# EEG.net
KiCad netlist of a schematic drawn in EAGLE
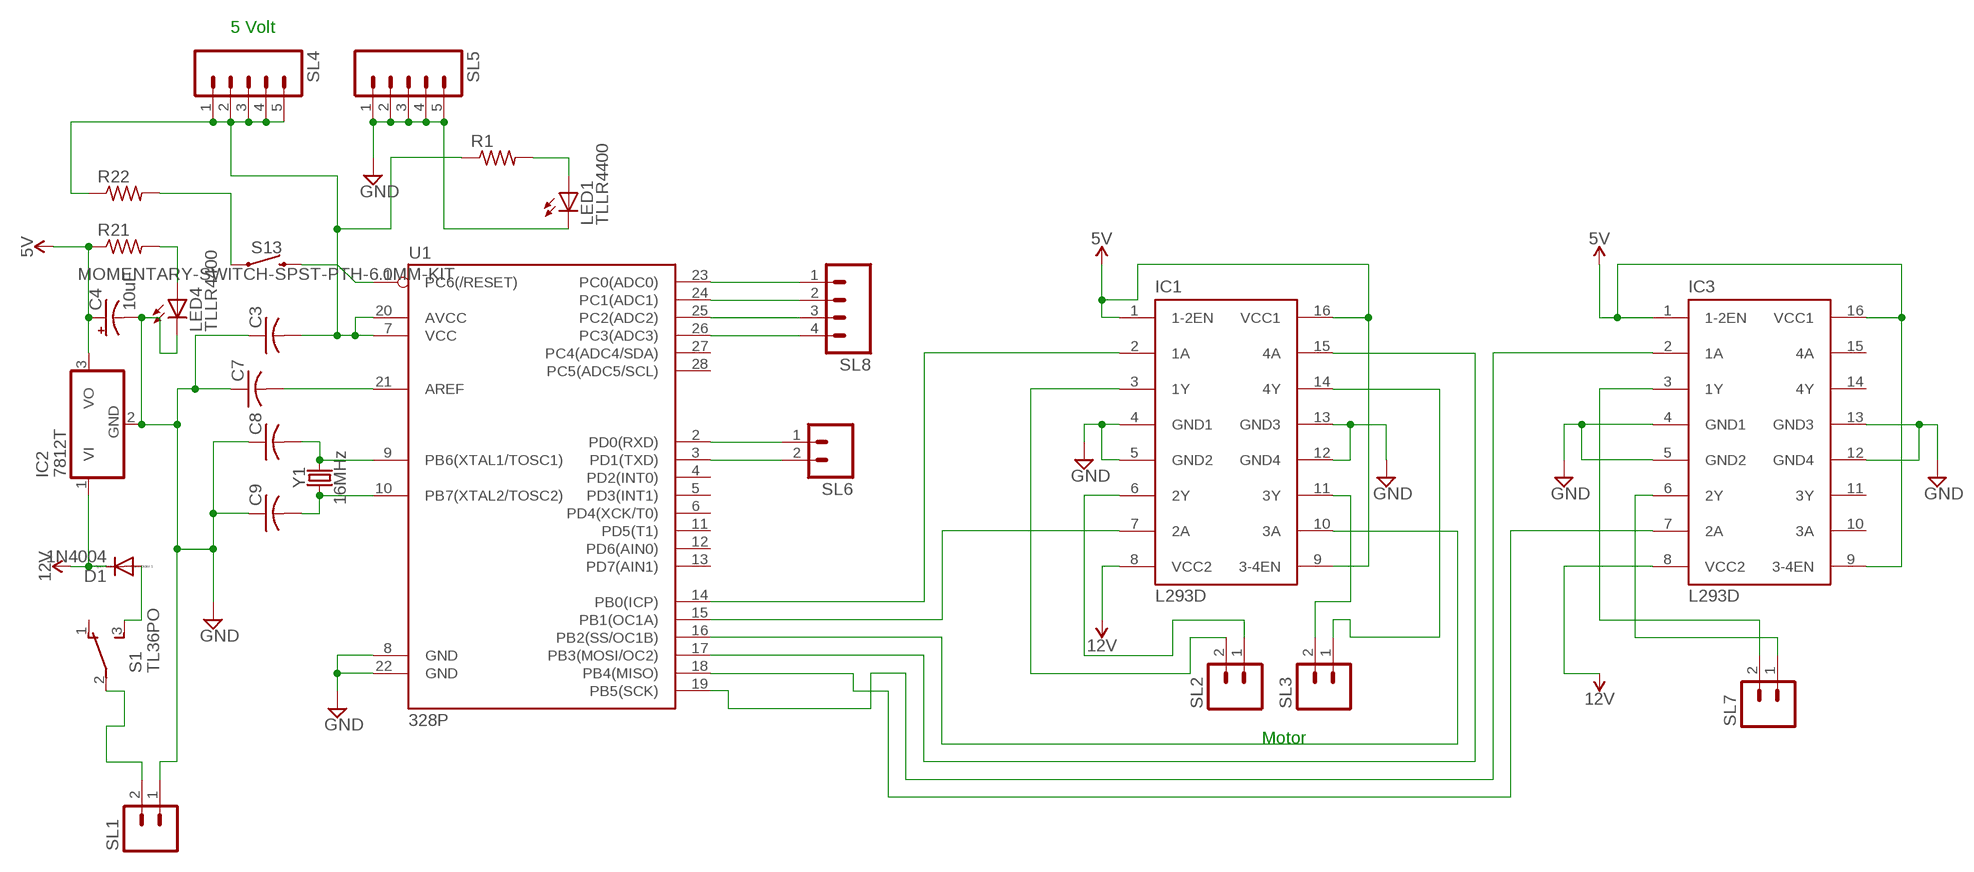
[diagram p0: schematic, sheet 1]

(export (version "E")
  (design (tool "Eeschema 10.0.6"))
  (components
    (comp (ref "C3")
      (value "C-US025-025X050")
      (footprint "eagle-import:C025-025X050")
      (libsource (lib "eagle-import") (part "C-US025-025X050"))
    )
    (comp (ref "C4")
      (value "10uF")
      (footprint "eagle-import:CPOL-RADIAL-2.5MM-5MM-KIT")
      (libsource (lib "eagle-import") (part "10UF-POLAR-RADIAL-2.5MM-KIT-25V-20%"))
    )
    (comp (ref "C7")
      (value "C-US025-025X050")
      (footprint "eagle-import:C025-025X050")
      (libsource (lib "eagle-import") (part "C-US025-025X050"))
    )
    (comp (ref "C8")
      (value "C-US025-025X050")
      (footprint "eagle-import:C025-025X050")
      (libsource (lib "eagle-import") (part "C-US025-025X050"))
    )
    (comp (ref "C9")
      (value "C-US025-025X050")
      (footprint "eagle-import:C025-025X050")
      (libsource (lib "eagle-import") (part "C-US025-025X050"))
    )
    (comp (ref "D1")
      (value "1N4004")
      (footprint "eagle-import:DO41-10")
      (libsource (lib "eagle-import") (part "1N4004"))
    )
    (comp (ref "IC1")
      (value "L293D")
      (footprint "eagle-import:DIL16")
      (libsource (lib "eagle-import") (part "L293D"))
    )
    (comp (ref "IC2")
      (value "7812T")
      (footprint "eagle-import:TO220H")
      (libsource (lib "eagle-import") (part "78T12"))
    )
    (comp (ref "IC3")
      (value "L293D")
      (footprint "eagle-import:DIL16")
      (libsource (lib "eagle-import") (part "L293D"))
    )
    (comp (ref "LED1")
      (value "TLLR4400")
      (footprint "eagle-import:LED3MM")
      (fields (field (name "MF") "VISHAY SEMICONDUCTOR"))
      (libsource (lib "eagle-import") (part "TLLR4400"))
    )
    (comp (ref "LED4")
      (value "TLLR4400")
      (footprint "eagle-import:LED3MM")
      (fields (field (name "MF") "VISHAY SEMICONDUCTOR"))
      (libsource (lib "eagle-import") (part "TLLR4400"))
    )
    (comp (ref "R1")
      (value "R-US_0207/12")
      (footprint "eagle-import:0207_12")
      (libsource (lib "eagle-import") (part "R-US_0207/12"))
    )
    (comp (ref "R21")
      (value "R-US_0207/12")
      (footprint "eagle-import:0207_12")
      (libsource (lib "eagle-import") (part "R-US_0207/12"))
    )
    (comp (ref "R22")
      (value "R-US_0207/12")
      (footprint "eagle-import:0207_12")
      (libsource (lib "eagle-import") (part "R-US_0207/12"))
    )
    (comp (ref "S1")
      (value "TL36PO")
      (footprint "eagle-import:TL3XPO")
      (libsource (lib "eagle-import") (part "TL36PO"))
    )
    (comp (ref "S13")
      (value "MOMENTARY-SWITCH-SPST-PTH-6.0MM-KIT")
      (footprint "eagle-import:TACTILE_SWITCH_PTH_6.0MM_KIT")
      (libsource (lib "eagle-import") (part "MOMENTARY-SWITCH-SPST-PTH-6.0MM-KIT"))
    )
    (comp (ref "SL1")
      (value "MA02")
      (footprint "eagle-import:02PA")
      (libsource (lib "eagle-import") (part "MA02"))
    )
    (comp (ref "SL2")
      (value "MA02")
      (footprint "eagle-import:02PA")
      (libsource (lib "eagle-import") (part "MA02"))
    )
    (comp (ref "SL3")
      (value "MA02")
      (footprint "eagle-import:02PA")
      (libsource (lib "eagle-import") (part "MA02"))
    )
    (comp (ref "SL4")
      (value "MA05")
      (footprint "eagle-import:05PA")
      (libsource (lib "eagle-import") (part "MA05"))
    )
    (comp (ref "SL5")
      (value "MA05")
      (footprint "eagle-import:05PA")
      (libsource (lib "eagle-import") (part "MA05"))
    )
    (comp (ref "SL6")
      (value "MA02")
      (footprint "eagle-import:02PA")
      (libsource (lib "eagle-import") (part "MA02"))
    )
    (comp (ref "SL7")
      (value "MA02")
      (footprint "eagle-import:02PA")
      (libsource (lib "eagle-import") (part "MA02"))
    )
    (comp (ref "SL8")
      (value "MA04")
      (footprint "eagle-import:04PA")
      (libsource (lib "eagle-import") (part "MA04"))
    )
    (comp (ref "U1")
      (value "328P")
      (footprint "eagle-import:DIP28")
      (libsource (lib "eagle-import") (part "ATMEGA328P_PDIP"))
    )
    (comp (ref "Y1")
      (value "16MHz")
      (footprint "eagle-import:HC49US")
      (libsource (lib "eagle-import") (part "CRYSTAL-16MHZPTH-HC49US"))
    )
  )
  (nets
    (net (code "1") (name "5V") (class "Default")
      (node (ref "C4") (pin "1") (pinfunction "+_1") (pintype "passive"))
      (node (ref "IC1") (pin "1") (pinfunction "1-2EN_1") (pintype "input"))
      (node (ref "IC1") (pin "16") (pinfunction "VCC1_16") (pintype "power_in"))
      (node (ref "IC1") (pin "9") (pinfunction "3-4EN_9") (pintype "input"))
      (node (ref "IC2") (pin "3") (pinfunction "VO_3") (pintype "passive"))
      (node (ref "IC3") (pin "1") (pinfunction "1-2EN_1") (pintype "input"))
      (node (ref "IC3") (pin "16") (pinfunction "VCC1_16") (pintype "power_in"))
      (node (ref "IC3") (pin "9") (pinfunction "3-4EN_9") (pintype "input"))
      (node (ref "R21") (pin "1") (pinfunction "1_1") (pintype "passive"))
    )
    (net (code "2") (name "12V") (class "Default")
      (node (ref "D1") (pin "C") (pinfunction "C_C") (pintype "passive"))
      (node (ref "IC1") (pin "8") (pinfunction "VCC2_8") (pintype "power_in"))
      (node (ref "IC2") (pin "1") (pinfunction "VI_1") (pintype "input"))
      (node (ref "IC3") (pin "8") (pinfunction "VCC2_8") (pintype "power_in"))
    )
    (net (code "3") (name "GND") (class "Default")
      (node (ref "C3") (pin "1") (pinfunction "1_1") (pintype "passive"))
      (node (ref "C4") (pin "2") (pinfunction "-_2") (pintype "passive"))
      (node (ref "C7") (pin "1") (pinfunction "1_1") (pintype "passive"))
      (node (ref "C8") (pin "1") (pinfunction "1_1") (pintype "passive"))
      (node (ref "C9") (pin "1") (pinfunction "1_1") (pintype "passive"))
      (node (ref "IC1") (pin "12") (pinfunction "GND4_12") (pintype "power_in"))
      (node (ref "IC1") (pin "13") (pinfunction "GND3_13") (pintype "power_in"))
      (node (ref "IC1") (pin "4") (pinfunction "GND1_4") (pintype "power_in"))
      (node (ref "IC1") (pin "5") (pinfunction "GND2_5") (pintype "power_in"))
      (node (ref "IC2") (pin "2") (pinfunction "GND_2") (pintype "passive"))
      (node (ref "IC3") (pin "12") (pinfunction "GND4_12") (pintype "power_in"))
      (node (ref "IC3") (pin "13") (pinfunction "GND3_13") (pintype "power_in"))
      (node (ref "IC3") (pin "4") (pinfunction "GND1_4") (pintype "power_in"))
      (node (ref "IC3") (pin "5") (pinfunction "GND2_5") (pintype "power_in"))
      (node (ref "LED1") (pin "K") (pinfunction "C_K") (pintype "passive"))
      (node (ref "LED4") (pin "K") (pinfunction "C_K") (pintype "passive"))
      (node (ref "SL1") (pin "1") (pinfunction "1_1") (pintype "passive"))
      (node (ref "SL5") (pin "1") (pinfunction "1_1") (pintype "passive"))
      (node (ref "SL5") (pin "2") (pinfunction "2_2") (pintype "passive"))
      (node (ref "SL5") (pin "3") (pinfunction "3_3") (pintype "passive"))
      (node (ref "SL5") (pin "4") (pinfunction "4_4") (pintype "passive"))
      (node (ref "SL5") (pin "5") (pinfunction "5_5") (pintype "passive"))
      (node (ref "U1") (pin "22") (pinfunction "GND_22") (pintype "bidirectional"))
      (node (ref "U1") (pin "8") (pinfunction "GND_8") (pintype "bidirectional"))
    )
    (net (code "4") (name "Net-(IC1-1A)") (class "Default")
      (node (ref "IC1") (pin "2") (pinfunction "1A_2") (pintype "input"))
      (node (ref "U1") (pin "14") (pinfunction "PB0(ICP)_14") (pintype "bidirectional"))
    )
    (net (code "5") (name "Net-(IC1-1Y)") (class "Default")
      (node (ref "IC1") (pin "3") (pinfunction "1Y_3") (pintype "output"))
      (node (ref "SL2") (pin "2") (pinfunction "2_2") (pintype "passive"))
    )
    (net (code "6") (name "Net-(IC1-2A)") (class "Default")
      (node (ref "IC1") (pin "7") (pinfunction "2A_7") (pintype "input"))
      (node (ref "U1") (pin "15") (pinfunction "PB1(OC1A)_15") (pintype "bidirectional"))
    )
    (net (code "7") (name "Net-(IC1-2Y)") (class "Default")
      (node (ref "IC1") (pin "6") (pinfunction "2Y_6") (pintype "output"))
      (node (ref "SL2") (pin "1") (pinfunction "1_1") (pintype "passive"))
    )
    (net (code "8") (name "Net-(IC1-3A)") (class "Default")
      (node (ref "IC1") (pin "10") (pinfunction "3A_10") (pintype "input"))
      (node (ref "U1") (pin "16") (pinfunction "PB2(SS/OC1B)_16") (pintype "bidirectional"))
    )
    (net (code "9") (name "Net-(IC1-3Y)") (class "Default")
      (node (ref "IC1") (pin "11") (pinfunction "3Y_11") (pintype "output"))
      (node (ref "SL3") (pin "2") (pinfunction "2_2") (pintype "passive"))
    )
    (net (code "10") (name "Net-(IC1-4A)") (class "Default")
      (node (ref "IC1") (pin "15") (pinfunction "4A_15") (pintype "input"))
      (node (ref "U1") (pin "17") (pinfunction "PB3(MOSI/OC2)_17") (pintype "bidirectional"))
    )
    (net (code "11") (name "Net-(IC1-4Y)") (class "Default")
      (node (ref "IC1") (pin "14") (pinfunction "4Y_14") (pintype "output"))
      (node (ref "SL3") (pin "1") (pinfunction "1_1") (pintype "passive"))
    )
    (net (code "12") (name "Net-(IC3-1A)") (class "Default")
      (node (ref "IC3") (pin "2") (pinfunction "1A_2") (pintype "input"))
      (node (ref "U1") (pin "19") (pinfunction "PB5(SCK)_19") (pintype "bidirectional"))
    )
    (net (code "13") (name "Net-(IC3-1Y)") (class "Default")
      (node (ref "IC3") (pin "3") (pinfunction "1Y_3") (pintype "output"))
      (node (ref "SL7") (pin "2") (pinfunction "2_2") (pintype "passive"))
    )
    (net (code "14") (name "Net-(IC3-2A)") (class "Default")
      (node (ref "IC3") (pin "7") (pinfunction "2A_7") (pintype "input"))
      (node (ref "U1") (pin "18") (pinfunction "PB4(MISO)_18") (pintype "bidirectional"))
    )
    (net (code "15") (name "Net-(IC3-2Y)") (class "Default")
      (node (ref "IC3") (pin "6") (pinfunction "2Y_6") (pintype "output"))
      (node (ref "SL7") (pin "1") (pinfunction "1_1") (pintype "passive"))
    )
    (net (code "16") (name "Net-(LED1-PadA)") (class "Default")
      (node (ref "LED1") (pin "A") (pinfunction "A_A") (pintype "passive"))
      (node (ref "R1") (pin "2") (pinfunction "2_2") (pintype "passive"))
    )
    (net (code "17") (name "Net-(LED4-PadA)") (class "Default")
      (node (ref "LED4") (pin "A") (pinfunction "A_A") (pintype "passive"))
      (node (ref "R21") (pin "2") (pinfunction "2_2") (pintype "passive"))
    )
    (net (code "18") (name "Net-(R22-Pad2)") (class "Default")
      (node (ref "R22") (pin "2") (pinfunction "2_2") (pintype "passive"))
      (node (ref "S13") (pin "1") (pinfunction "1_1") (pintype "passive"))
    )
    (net (code "19") (name "Net-(S1-P)") (class "Default")
      (node (ref "S1") (pin "2") (pinfunction "P_2") (pintype "passive"))
      (node (ref "SL1") (pin "2") (pinfunction "2_2") (pintype "passive"))
    )
    (net (code "20") (name "Net-(S1-S)") (class "Default")
      (node (ref "D1") (pin "A") (pinfunction "A_A") (pintype "passive"))
      (node (ref "S1") (pin "3") (pinfunction "S_3") (pintype "passive"))
    )
    (net (code "21") (name "Net-(S13-2)") (class "Default")
      (node (ref "S13") (pin "3") (pinfunction "2_3") (pintype "passive"))
      (node (ref "U1") (pin "1") (pinfunction "PC6(/RESET)_1") (pintype "bidirectional"))
    )
    (net (code "22") (name "Net-(U1-AREF)") (class "Default")
      (node (ref "C7") (pin "2") (pinfunction "2_2") (pintype "passive"))
      (node (ref "U1") (pin "21") (pinfunction "AREF_21") (pintype "bidirectional"))
    )
    (net (code "23") (name "Net-(U1-AVCC)") (class "Default")
      (node (ref "C3") (pin "2") (pinfunction "2_2") (pintype "passive"))
      (node (ref "R1") (pin "1") (pinfunction "1_1") (pintype "passive"))
      (node (ref "R22") (pin "1") (pinfunction "1_1") (pintype "passive"))
      (node (ref "SL4") (pin "1") (pinfunction "1_1") (pintype "passive"))
      (node (ref "SL4") (pin "2") (pinfunction "2_2") (pintype "passive"))
      (node (ref "SL4") (pin "3") (pinfunction "3_3") (pintype "passive"))
      (node (ref "SL4") (pin "4") (pinfunction "4_4") (pintype "passive"))
      (node (ref "SL4") (pin "5") (pinfunction "5_5") (pintype "passive"))
      (node (ref "U1") (pin "20") (pinfunction "AVCC_20") (pintype "bidirectional"))
      (node (ref "U1") (pin "7") (pinfunction "VCC_7") (pintype "bidirectional"))
    )
    (net (code "24") (name "Net-(U1-PB6(XTAL1{slash}TOSC1))") (class "Default")
      (node (ref "C8") (pin "2") (pinfunction "2_2") (pintype "passive"))
      (node (ref "U1") (pin "9") (pinfunction "PB6(XTAL1/TOSC1)_9") (pintype "bidirectional"))
      (node (ref "Y1") (pin "2") (pinfunction "2_2") (pintype "passive"))
    )
    (net (code "25") (name "Net-(U1-PB7(XTAL2{slash}TOSC2))") (class "Default")
      (node (ref "C9") (pin "2") (pinfunction "2_2") (pintype "passive"))
      (node (ref "U1") (pin "10") (pinfunction "PB7(XTAL2/TOSC2)_10") (pintype "bidirectional"))
      (node (ref "Y1") (pin "1") (pinfunction "1_1") (pintype "passive"))
    )
    (net (code "26") (name "Net-(U1-PC0(ADC0))") (class "Default")
      (node (ref "SL8") (pin "1") (pinfunction "1_1") (pintype "passive"))
      (node (ref "U1") (pin "23") (pinfunction "PC0(ADC0)_23") (pintype "bidirectional"))
    )
    (net (code "27") (name "Net-(U1-PC1(ADC1))") (class "Default")
      (node (ref "SL8") (pin "2") (pinfunction "2_2") (pintype "passive"))
      (node (ref "U1") (pin "24") (pinfunction "PC1(ADC1)_24") (pintype "bidirectional"))
    )
    (net (code "28") (name "Net-(U1-PC2(ADC2))") (class "Default")
      (node (ref "SL8") (pin "3") (pinfunction "3_3") (pintype "passive"))
      (node (ref "U1") (pin "25") (pinfunction "PC2(ADC2)_25") (pintype "bidirectional"))
    )
    (net (code "29") (name "Net-(U1-PC3(ADC3))") (class "Default")
      (node (ref "SL8") (pin "4") (pinfunction "4_4") (pintype "passive"))
      (node (ref "U1") (pin "26") (pinfunction "PC3(ADC3)_26") (pintype "bidirectional"))
    )
    (net (code "30") (name "Net-(U1-PD0(RXD))") (class "Default")
      (node (ref "SL6") (pin "1") (pinfunction "1_1") (pintype "passive"))
      (node (ref "U1") (pin "2") (pinfunction "PD0(RXD)_2") (pintype "bidirectional"))
    )
    (net (code "31") (name "Net-(U1-PD1(TXD))") (class "Default")
      (node (ref "SL6") (pin "2") (pinfunction "2_2") (pintype "passive"))
      (node (ref "U1") (pin "3") (pinfunction "PD1(TXD)_3") (pintype "bidirectional"))
    )
    (net (code "32") (name "unconnected-(IC3-3A-Pad10)") (class "Default")
      (node (ref "IC3") (pin "10") (pinfunction "3A_10") (pintype "input"))
    )
    (net (code "33") (name "unconnected-(IC3-3Y-Pad11)") (class "Default")
      (node (ref "IC3") (pin "11") (pinfunction "3Y_11") (pintype "output"))
    )
    (net (code "34") (name "unconnected-(IC3-4A-Pad15)") (class "Default")
      (node (ref "IC3") (pin "15") (pinfunction "4A_15") (pintype "input"))
    )
    (net (code "35") (name "unconnected-(IC3-4Y-Pad14)") (class "Default")
      (node (ref "IC3") (pin "14") (pinfunction "4Y_14") (pintype "output"))
    )
    (net (code "36") (name "unconnected-(S1-O-Pad1)") (class "Default")
      (node (ref "S1") (pin "1") (pinfunction "O_1") (pintype "passive"))
    )
    (net (code "37") (name "unconnected-(U1-PC4(ADC4{slash}SDA)-Pad27)") (class "Default")
      (node (ref "U1") (pin "27") (pinfunction "PC4(ADC4/SDA)_27") (pintype "bidirectional"))
    )
    (net (code "38") (name "unconnected-(U1-PC5(ADC5{slash}SCL)-Pad28)") (class "Default")
      (node (ref "U1") (pin "28") (pinfunction "PC5(ADC5/SCL)_28") (pintype "bidirectional"))
    )
    (net (code "39") (name "unconnected-(U1-PD2(INT0)-Pad4)") (class "Default")
      (node (ref "U1") (pin "4") (pinfunction "PD2(INT0)_4") (pintype "bidirectional"))
    )
    (net (code "40") (name "unconnected-(U1-PD3(INT1)-Pad5)") (class "Default")
      (node (ref "U1") (pin "5") (pinfunction "PD3(INT1)_5") (pintype "bidirectional"))
    )
    (net (code "41") (name "unconnected-(U1-PD4(XCK{slash}T0)-Pad6)") (class "Default")
      (node (ref "U1") (pin "6") (pinfunction "PD4(XCK/T0)_6") (pintype "bidirectional"))
    )
    (net (code "42") (name "unconnected-(U1-PD5(T1)-Pad11)") (class "Default")
      (node (ref "U1") (pin "11") (pinfunction "PD5(T1)_11") (pintype "bidirectional"))
    )
    (net (code "43") (name "unconnected-(U1-PD6(AIN0)-Pad12)") (class "Default")
      (node (ref "U1") (pin "12") (pinfunction "PD6(AIN0)_12") (pintype "bidirectional"))
    )
    (net (code "44") (name "unconnected-(U1-PD7(AIN1)-Pad13)") (class "Default")
      (node (ref "U1") (pin "13") (pinfunction "PD7(AIN1)_13") (pintype "bidirectional"))
    )
  )
)
